# EFNMR_PROCESSOR_V1.net
KiCad netlist of a schematic drawn in Altium Designer
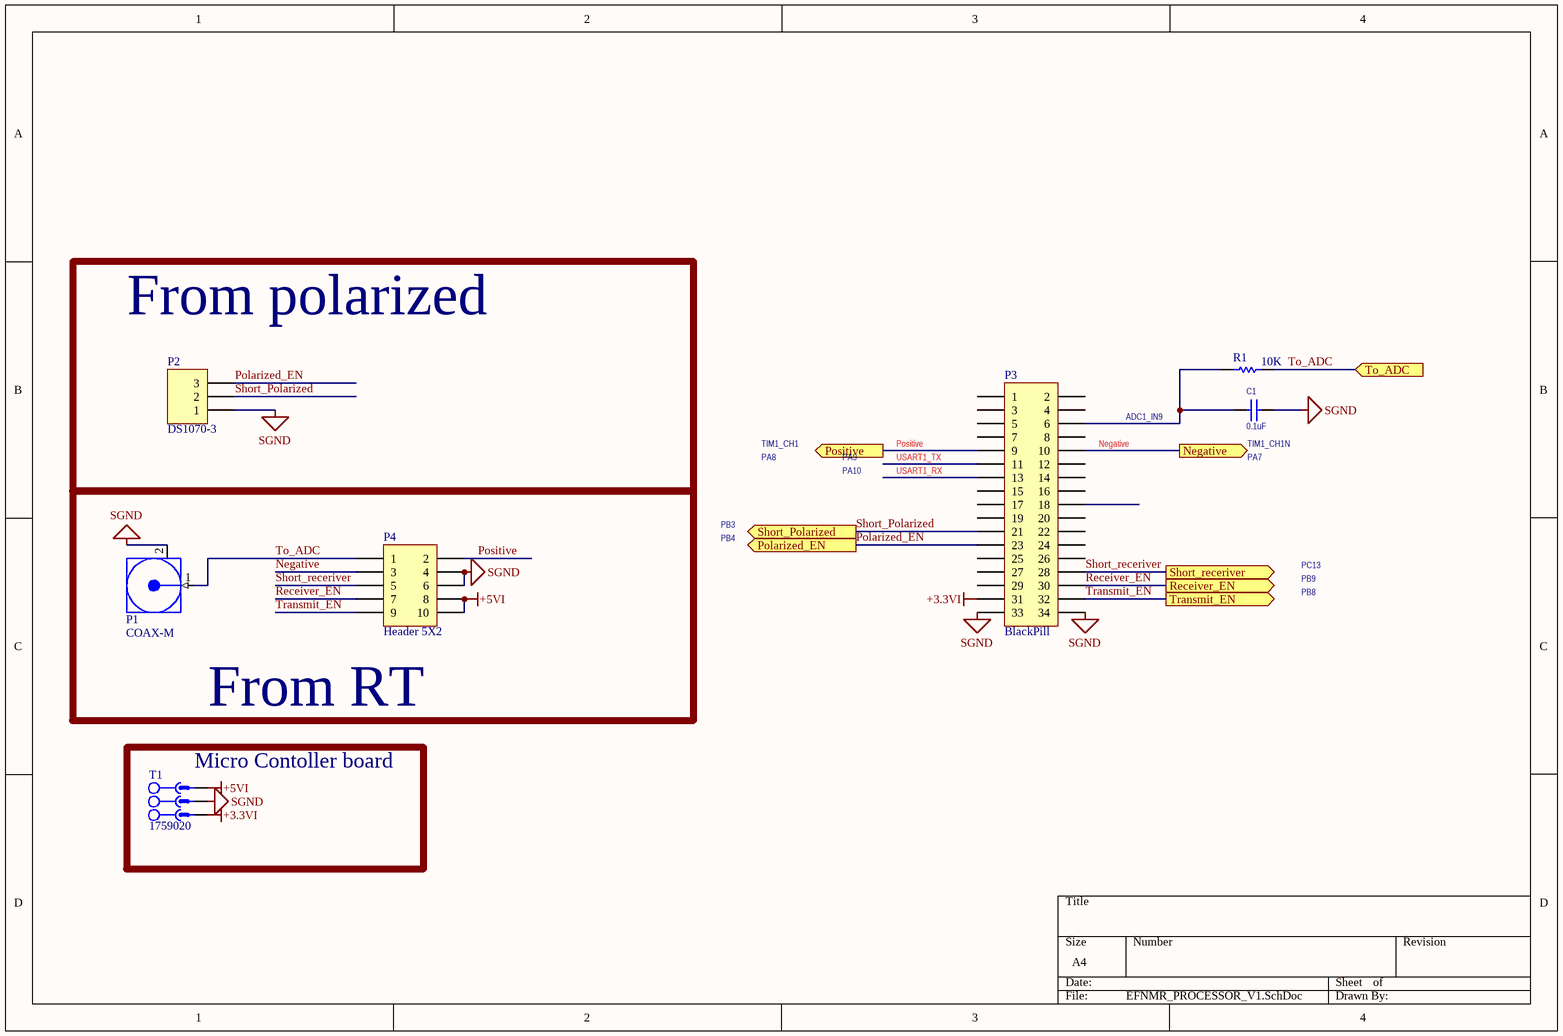
[diagram p0: EFNMR_PROCESSOR_V1.SchDoc]

(export (version "E")
  (design (tool "Eeschema 10.0.6"))
  (components
    (comp (ref "C1")
      (value "0.1uF")
      (footprint "CAP0805")
      (description "CAP 0805")
      (fields (field (name "DESIGNER") "Abbas Basereh"))
      (libsource (lib "Mofidi3D") (part "CAP SMD 0805"))
    )
    (comp (ref "P1")
      (value "COAX-M")
      (footprint "SMA_RA_F")
      (description "RF Coaxial PCB Connector, MMCX; Thru-Hole, Vertical Mount Plug,  50 Ohm Impedance")
      (fields (field (name "PUBLISHER") "Altium Limited"))
      (libsource (lib "Miscellaneous Connectors") (part "COAX-M"))
    )
    (comp (ref "P2")
      (value "DS1070-3")
      (footprint "DS1070-3-COMCON")
      (description "Header, 3-Pin")
      (fields (field (name "PUBLISHER") "Altium Limited"))
      (libsource (lib "Miscellaneous Connectors") (part "Header 3"))
    )
    (comp (ref "P3")
      (value "BlackPill")
      (footprint "BlackPill")
      (description "Header, 17-Pin, Dual row")
      (fields (field (name "PUBLISHER") "Altium Limited"))
      (libsource (lib "Miscellaneous Connectors") (part "Header 17X2"))
    )
    (comp (ref "P4")
      (value "Header 5X2")
      (footprint "IDC2.54-10PIN WITH CABLE")
      (description "Header, 5-Pin, Dual row")
      (fields (field (name "PUBLISHER") "Altium Limited"))
      (libsource (lib "Miscellaneous Connectors") (part "Header 5X2"))
    )
    (comp (ref "R1")
      (value "10K")
      (footprint "RES0805")
      (description "Resistor")
      (fields (field (name "PUBLISHER") "Altium Limited"))
      (libsource (lib "Miscellaneous Devices") (part "Res1"))
    )
    (comp (ref "T1")
      (value "1759020")
      (footprint "MSTB 2,5/3-G-5,08")
      (description "3 Pitch: 5.08 mm Color: green Contact surface: Tin Assembly")
      (fields
        (field (name "MANUFACTURER") "PHOENIX CONTACT")
        (field (name "VOLTAGE") "320 V")
        (field (name "DESIGNER") "ABBAS BASEREH")
      )
      (libsource (lib "Mofidi3D") (part "CON_Phoenix_MSTB_03"))
    )
  )
  (nets
    (net (code "1") (name "+3.3VI") (class "Default")
      (node (ref "P3") (pin "31") (pinfunction "31_31") (pintype "passive"))
      (node (ref "T1") (pin "1") (pinfunction "1_1") (pintype "passive"))
    )
    (net (code "2") (name "+5VI") (class "Default")
      (node (ref "P4") (pin "10") (pinfunction "10_10") (pintype "passive"))
      (node (ref "P4") (pin "8") (pinfunction "8_8") (pintype "passive"))
      (node (ref "T1") (pin "3") (pinfunction "3_3") (pintype "passive"))
    )
    (net (code "3") (name "/Negative") (class "Default")
      (node (ref "P3") (pin "10") (pinfunction "10_10") (pintype "passive"))
      (node (ref "P4") (pin "3") (pinfunction "3_3") (pintype "passive"))
    )
    (net (code "4") (name "/Polarized_EN") (class "Default")
      (node (ref "P2") (pin "3") (pinfunction "3_3") (pintype "passive"))
      (node (ref "P3") (pin "23") (pinfunction "23_23") (pintype "passive"))
    )
    (net (code "5") (name "/Positive") (class "Default")
      (node (ref "P3") (pin "9") (pinfunction "9_9") (pintype "passive"))
      (node (ref "P4") (pin "2") (pinfunction "2_2") (pintype "passive"))
    )
    (net (code "6") (name "/Receiver_EN") (class "Default")
      (node (ref "P3") (pin "30") (pinfunction "30_30") (pintype "passive"))
      (node (ref "P4") (pin "7") (pinfunction "7_7") (pintype "passive"))
    )
    (net (code "7") (name "/Short_Polarized") (class "Default")
      (node (ref "P2") (pin "2") (pinfunction "2_2") (pintype "passive"))
      (node (ref "P3") (pin "21") (pinfunction "21_21") (pintype "passive"))
    )
    (net (code "8") (name "/Short_receriver") (class "Default")
      (node (ref "P3") (pin "28") (pinfunction "28_28") (pintype "passive"))
      (node (ref "P4") (pin "5") (pinfunction "5_5") (pintype "passive"))
    )
    (net (code "9") (name "/To_ADC") (class "Default")
      (node (ref "P1") (pin "1") (pinfunction "Signal_1") (pintype "input"))
      (node (ref "P4") (pin "1") (pinfunction "1_1") (pintype "passive"))
      (node (ref "R1") (pin "2") (pinfunction "2_2") (pintype "passive"))
    )
    (net (code "10") (name "/Transmit_EN") (class "Default")
      (node (ref "P3") (pin "32") (pinfunction "32_32") (pintype "passive"))
      (node (ref "P4") (pin "9") (pinfunction "9_9") (pintype "passive"))
    )
    (net (code "11") (name "/USART1_RX") (class "Default")
      (node (ref "P3") (pin "13") (pinfunction "13_13") (pintype "passive"))
    )
    (net (code "12") (name "/USART1_TX") (class "Default")
      (node (ref "P3") (pin "11") (pinfunction "11_11") (pintype "passive"))
    )
    (net (code "13") (name "Net-(C1-Pad1)") (class "Default")
      (node (ref "C1") (pin "1") (pinfunction "1_1") (pintype "passive"))
      (node (ref "P3") (pin "6") (pinfunction "6_6") (pintype "passive"))
      (node (ref "R1") (pin "1") (pinfunction "1_1") (pintype "passive"))
    )
    (net (code "14") (name "SGND") (class "Default")
      (node (ref "C1") (pin "2") (pinfunction "2_2") (pintype "passive"))
      (node (ref "P1") (pin "2") (pinfunction "GND_2") (pintype "power_in"))
      (node (ref "P2") (pin "1") (pinfunction "1_1") (pintype "passive"))
      (node (ref "P3") (pin "33") (pinfunction "33_33") (pintype "passive"))
      (node (ref "P3") (pin "34") (pinfunction "34_34") (pintype "passive"))
      (node (ref "P4") (pin "4") (pinfunction "4_4") (pintype "passive"))
      (node (ref "P4") (pin "6") (pinfunction "6_6") (pintype "passive"))
      (node (ref "T1") (pin "2") (pinfunction "2_2") (pintype "passive"))
    )
    (net (code "15") (name "unconnected-(P3-Pad1)") (class "Default")
      (node (ref "P3") (pin "1") (pinfunction "1_1") (pintype "passive"))
    )
    (net (code "16") (name "unconnected-(P3-Pad2)") (class "Default")
      (node (ref "P3") (pin "2") (pinfunction "2_2") (pintype "passive"))
    )
    (net (code "17") (name "unconnected-(P3-Pad3)") (class "Default")
      (node (ref "P3") (pin "3") (pinfunction "3_3") (pintype "passive"))
    )
    (net (code "18") (name "unconnected-(P3-Pad4)") (class "Default")
      (node (ref "P3") (pin "4") (pinfunction "4_4") (pintype "passive"))
    )
    (net (code "19") (name "unconnected-(P3-Pad5)") (class "Default")
      (node (ref "P3") (pin "5") (pinfunction "5_5") (pintype "passive"))
    )
    (net (code "20") (name "unconnected-(P3-Pad7)") (class "Default")
      (node (ref "P3") (pin "7") (pinfunction "7_7") (pintype "passive"))
    )
    (net (code "21") (name "unconnected-(P3-Pad8)") (class "Default")
      (node (ref "P3") (pin "8") (pinfunction "8_8") (pintype "passive"))
    )
    (net (code "22") (name "unconnected-(P3-Pad12)") (class "Default")
      (node (ref "P3") (pin "12") (pinfunction "12_12") (pintype "passive"))
    )
    (net (code "23") (name "unconnected-(P3-Pad14)") (class "Default")
      (node (ref "P3") (pin "14") (pinfunction "14_14") (pintype "passive"))
    )
    (net (code "24") (name "unconnected-(P3-Pad15)") (class "Default")
      (node (ref "P3") (pin "15") (pinfunction "15_15") (pintype "passive"))
    )
    (net (code "25") (name "unconnected-(P3-Pad16)") (class "Default")
      (node (ref "P3") (pin "16") (pinfunction "16_16") (pintype "passive"))
    )
    (net (code "26") (name "unconnected-(P3-Pad17)") (class "Default")
      (node (ref "P3") (pin "17") (pinfunction "17_17") (pintype "passive"))
    )
    (net (code "27") (name "unconnected-(P3-Pad18)") (class "Default")
      (node (ref "P3") (pin "18") (pinfunction "18_18") (pintype "passive"))
    )
    (net (code "28") (name "unconnected-(P3-Pad19)") (class "Default")
      (node (ref "P3") (pin "19") (pinfunction "19_19") (pintype "passive"))
    )
    (net (code "29") (name "unconnected-(P3-Pad20)") (class "Default")
      (node (ref "P3") (pin "20") (pinfunction "20_20") (pintype "passive"))
    )
    (net (code "30") (name "unconnected-(P3-Pad22)") (class "Default")
      (node (ref "P3") (pin "22") (pinfunction "22_22") (pintype "passive"))
    )
    (net (code "31") (name "unconnected-(P3-Pad24)") (class "Default")
      (node (ref "P3") (pin "24") (pinfunction "24_24") (pintype "passive"))
    )
    (net (code "32") (name "unconnected-(P3-Pad25)") (class "Default")
      (node (ref "P3") (pin "25") (pinfunction "25_25") (pintype "passive"))
    )
    (net (code "33") (name "unconnected-(P3-Pad26)") (class "Default")
      (node (ref "P3") (pin "26") (pinfunction "26_26") (pintype "passive"))
    )
    (net (code "34") (name "unconnected-(P3-Pad27)") (class "Default")
      (node (ref "P3") (pin "27") (pinfunction "27_27") (pintype "passive"))
    )
    (net (code "35") (name "unconnected-(P3-Pad29)") (class "Default")
      (node (ref "P3") (pin "29") (pinfunction "29_29") (pintype "passive"))
    )
  )
)
